# DarkDetector.net
KiCad netlist of a schematic drawn in EasyEDA
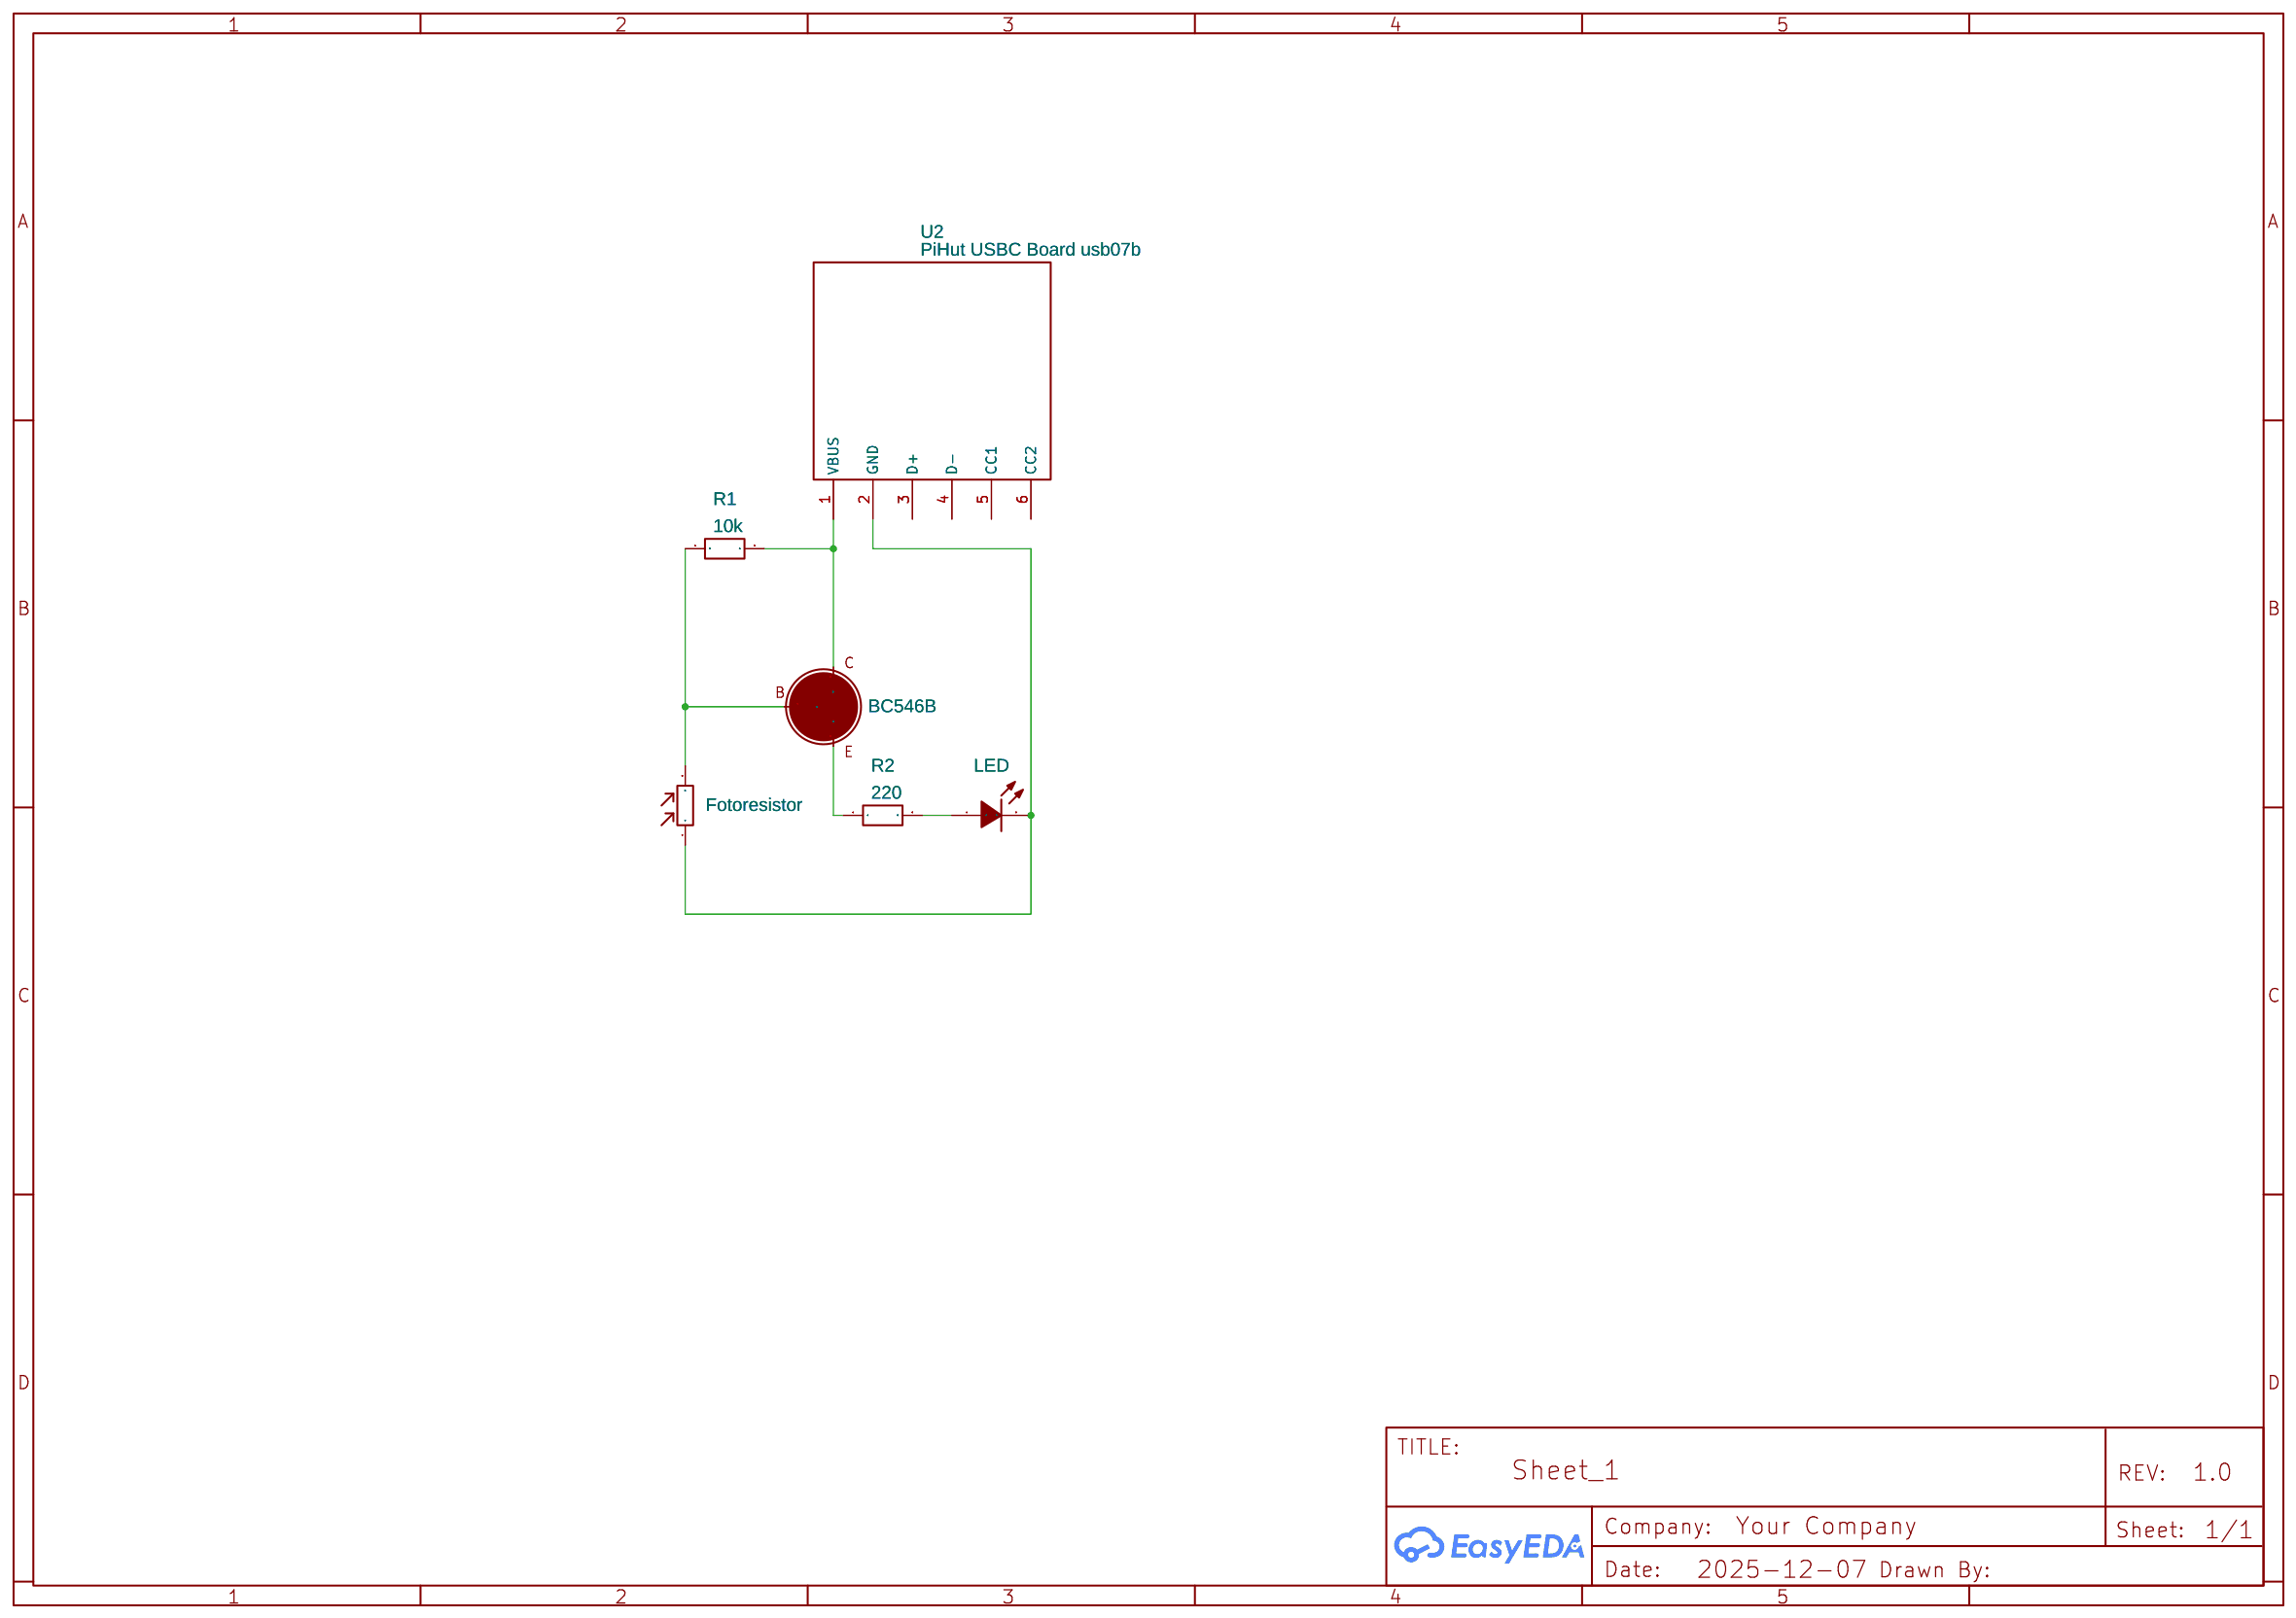
[diagram p0: schematic sheet]

(export (version "E")
  (design (tool "Eeschema 10.0.6"))
  (components
    (comp (ref "LED")
      (value "RED")
      (fields
        (field (name "Manufacturer Part") "19-217/R6C-AL1M2VY/3T")
        (field (name "Manufacturer") "EVERLIGHT(台湾亿光)")
      )
      (libsource (lib "") (part "LED-0603_R"))
    )
    (comp (ref "Q1")
      (value "BC546B")
      (fields (field (name "Manufacturer Part") "BC337") (field (name "Manufacturer") "CJ"))
      (libsource (lib "") (part "BC546B"))
    )
    (comp (ref "R1") (value "10k") (libsource (lib "") (part "R_0603_EU")))
    (comp (ref "R2") (value "220") (libsource (lib "") (part "R_0603_EU")))
    (comp (ref "U1") (value "Fotoresistor") (libsource (lib "") (part "Fotoresistor G")))
    (comp (ref "U2")
      (value "PiHut USBC Board usb07b")
      (fields (field (name "Manufacturer Part") "usb07b") (field (name "Manufacturer") "PiHut"))
      (libsource (lib "") (part "PiHut USBC Board usb07b"))
    )
  )
  (nets
    (net (code "1") (name "Net-(LED-Pad1)") (class "Default")
      (node (ref "LED") (pin "1") (pinfunction "1_1") (pintype "unspecified"))
      (node (ref "R2") (pin "2") (pinfunction "2_2") (pintype "unspecified"))
    )
    (net (code "2") (name "Net-(Q1-B)") (class "Default")
      (node (ref "Q1") (pin "2") (pinfunction "B_2") (pintype "unspecified"))
      (node (ref "R1") (pin "1") (pinfunction "1_1") (pintype "unspecified"))
      (node (ref "U1") (pin "2") (pinfunction "2_2") (pintype "input"))
    )
    (net (code "3") (name "Net-(Q1-C)") (class "Default")
      (node (ref "Q1") (pin "1") (pinfunction "C_1") (pintype "unspecified"))
      (node (ref "R1") (pin "2") (pinfunction "2_2") (pintype "unspecified"))
      (node (ref "U2") (pin "1") (pinfunction "VBUS_1") (pintype "unspecified"))
    )
    (net (code "4") (name "Net-(Q1-E)") (class "Default")
      (node (ref "Q1") (pin "3") (pinfunction "E_3") (pintype "unspecified"))
      (node (ref "R2") (pin "1") (pinfunction "1_1") (pintype "unspecified"))
    )
    (net (code "5") (name "Net-(U2-GND)") (class "Default")
      (node (ref "LED") (pin "2") (pinfunction "2_2") (pintype "unspecified"))
      (node (ref "U1") (pin "1") (pinfunction "1_1") (pintype "input"))
      (node (ref "U2") (pin "2") (pinfunction "GND_2") (pintype "unspecified"))
    )
    (net (code "6") (name "unconnected-(U2-CC1-Pad5)") (class "Default")
      (node (ref "U2") (pin "5") (pinfunction "CC1_5") (pintype "unspecified"))
    )
    (net (code "7") (name "unconnected-(U2-CC2-Pad6)") (class "Default")
      (node (ref "U2") (pin "6") (pinfunction "CC2_6") (pintype "unspecified"))
    )
    (net (code "8") (name "unconnected-(U2-D+-Pad3)") (class "Default")
      (node (ref "U2") (pin "3") (pinfunction "D+_3") (pintype "unspecified"))
    )
    (net (code "9") (name "unconnected-(U2-D--Pad4)") (class "Default")
      (node (ref "U2") (pin "4") (pinfunction "D-_4") (pintype "unspecified"))
    )
  )
)
